# CristmasVillage_Driver_1-1.net
KiCad netlist of a schematic drawn in EAGLE
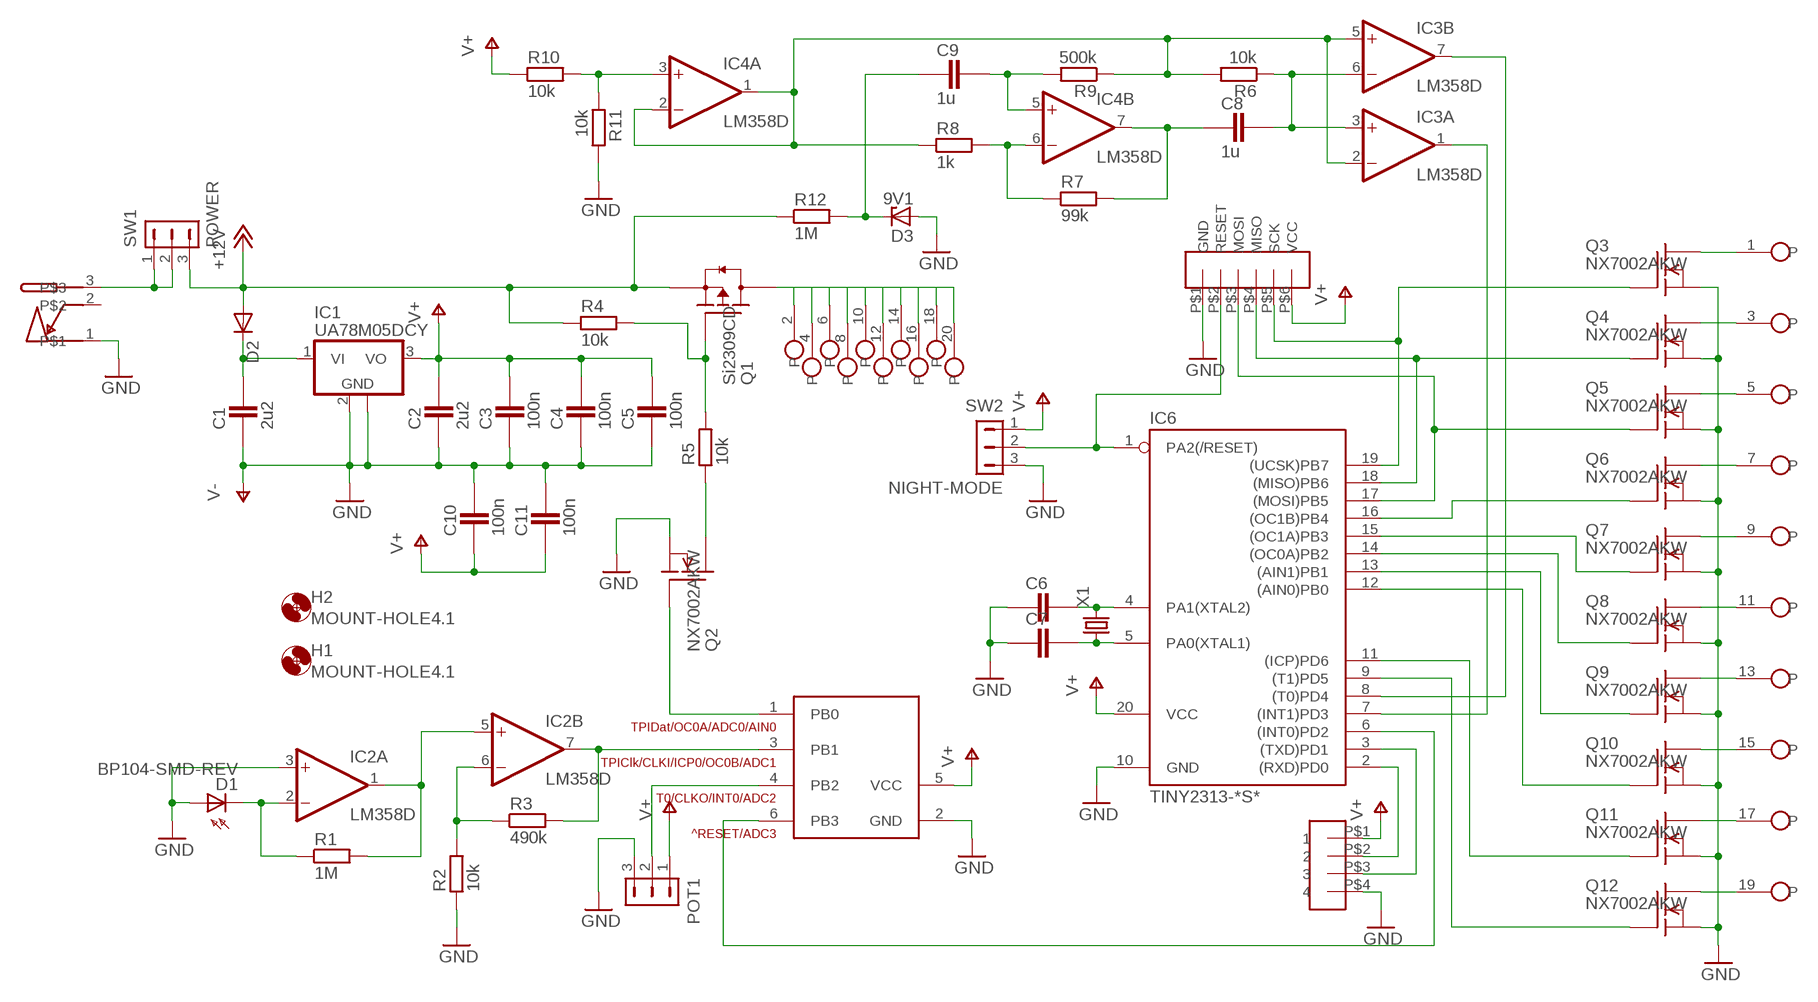
[diagram p0: schematic, sheet 1]

(export (version "E")
  (design (tool "Eeschema 10.0.6"))
  (components
    (comp (ref "C1")
      (value "2u2")
      (footprint "eagle-import:CAPC3215X168N")
      (libsource (lib "eagle-import") (part "CAPACITOR_1206"))
    )
    (comp (ref "C2")
      (value "2u2")
      (footprint "eagle-import:CAPC3215X168N")
      (libsource (lib "eagle-import") (part "CAPACITOR_1206"))
    )
    (comp (ref "C3")
      (value "100n")
      (footprint "eagle-import:CAPC1608X92N")
      (libsource (lib "eagle-import") (part "CAPACITOR_0603"))
    )
    (comp (ref "C4")
      (value "100n")
      (footprint "eagle-import:CAPC1608X92N")
      (libsource (lib "eagle-import") (part "CAPACITOR_0603"))
    )
    (comp (ref "C5")
      (value "100n")
      (footprint "eagle-import:CAPC1608X92N")
      (libsource (lib "eagle-import") (part "CAPACITOR_0603"))
    )
    (comp (ref "C6")
      (value "CAPACITOR_0603")
      (footprint "eagle-import:CAPC1608X92N")
      (libsource (lib "eagle-import") (part "CAPACITOR_0603"))
    )
    (comp (ref "C7")
      (value "CAPACITOR_0603")
      (footprint "eagle-import:CAPC1608X92N")
      (libsource (lib "eagle-import") (part "CAPACITOR_0603"))
    )
    (comp (ref "C8")
      (value "1u")
      (footprint "eagle-import:CAPC3215X168N")
      (libsource (lib "eagle-import") (part "CAPACITOR_1206"))
    )
    (comp (ref "C9")
      (value "1u")
      (footprint "eagle-import:CAPC3215X168N")
      (libsource (lib "eagle-import") (part "CAPACITOR_1206"))
    )
    (comp (ref "C10")
      (value "100n")
      (footprint "eagle-import:CAPC1608X92N")
      (libsource (lib "eagle-import") (part "CAPACITOR_0603"))
    )
    (comp (ref "C11")
      (value "100n")
      (footprint "eagle-import:CAPC1608X92N")
      (libsource (lib "eagle-import") (part "CAPACITOR_0603"))
    )
    (comp (ref "CN1")
      (value "MJ-180SMT")
      (footprint "eagle-import:MJ-180SMT")
      (libsource (lib "eagle-import") (part "MJ-180SMT"))
    )
    (comp (ref "CN2-PROG")
      (value "JST-6PSPI-SIDE-S6B")
      (footprint "eagle-import:6P-H")
      (libsource (lib "eagle-import") (part "JST-6PSPI-SIDE-S6B"))
    )
    (comp (ref "CN3-SERIAL")
      (value "JST-4PSIDE-S4B")
      (footprint "eagle-import:4P-H")
      (libsource (lib "eagle-import") (part "JST-4PSIDE-S4B"))
    )
    (comp (ref "CN5-LEDSTRIPS")
      (value "HDR_2X10_SIDE-MOUNT")
      (footprint "eagle-import:20PIN-10TOP-10BOT")
      (libsource (lib "eagle-import") (part "HDR_2X10_SIDE-MOUNT"))
    )
    (comp (ref "D1")
      (value "BP104-SMD-REV")
      (footprint "eagle-import:BR104SMDREV")
      (libsource (lib "eagle-import") (part "BP104-SMD-REV"))
    )
    (comp (ref "D2")
      (value "DIODE-MINIMELF")
      (footprint "eagle-import:MINIMELF")
      (libsource (lib "eagle-import") (part "DIODE-MINIMELF"))
    )
    (comp (ref "D3")
      (value "9V1")
      (footprint "eagle-import:SOT23")
      (libsource (lib "eagle-import") (part "ZENER-DIODESOT23"))
    )
    (comp (ref "H1")
      (value "MOUNT-HOLE4.1")
      (footprint "eagle-import:4,1")
      (libsource (lib "eagle-import") (part "MOUNT-HOLE4.1"))
    )
    (comp (ref "H2")
      (value "MOUNT-HOLE4.1")
      (footprint "eagle-import:4,1")
      (libsource (lib "eagle-import") (part "MOUNT-HOLE4.1"))
    )
    (comp (ref "IC1")
      (value "UA78M05DCY")
      (footprint "eagle-import:SOT223")
      (libsource (lib "eagle-import") (part "UA78MDCY05"))
    )
    (comp (ref "IC2")
      (value "LM358D")
      (footprint "eagle-import:SO08")
      (libsource (lib "eagle-import") (part "LM358D"))
    )
    (comp (ref "IC3")
      (value "LM358D")
      (footprint "eagle-import:SO08")
      (libsource (lib "eagle-import") (part "LM358D"))
    )
    (comp (ref "IC4")
      (value "LM358D")
      (footprint "eagle-import:SO08")
      (libsource (lib "eagle-import") (part "LM358D"))
    )
    (comp (ref "IC5")
      (value "ATTINY-4/5/9/10")
      (footprint "eagle-import:SOT23-6")
      (libsource (lib "eagle-import") (part "ATTINY-4/5/9/10"))
    )
    (comp (ref "IC6")
      (value "TINY2313-*S*")
      (footprint "eagle-import:SO20L$")
      (libsource (lib "eagle-import") (part "TINY2313-S"))
    )
    (comp (ref "POT1")
      (value "HDR-1X3-MTE-100")
      (footprint "eagle-import:MTE-100-3V")
      (libsource (lib "eagle-import") (part "HDR-1X3-MTE-100"))
    )
    (comp (ref "Q1")
      (value "Si2309CD")
      (footprint "eagle-import:SOT95P280X135-3N")
      (libsource (lib "eagle-import") (part "MOSFET-PCH_SOT-23"))
    )
    (comp (ref "Q2")
      (value "NX7002AKW")
      (footprint "eagle-import:SOT323R")
      (libsource (lib "eagle-import") (part "NX7002AKW"))
    )
    (comp (ref "Q3")
      (value "NX7002AKW")
      (footprint "eagle-import:SOT323R")
      (libsource (lib "eagle-import") (part "NX7002AKW"))
    )
    (comp (ref "Q4")
      (value "NX7002AKW")
      (footprint "eagle-import:SOT323R")
      (libsource (lib "eagle-import") (part "NX7002AKW"))
    )
    (comp (ref "Q5")
      (value "NX7002AKW")
      (footprint "eagle-import:SOT323R")
      (libsource (lib "eagle-import") (part "NX7002AKW"))
    )
    (comp (ref "Q6")
      (value "NX7002AKW")
      (footprint "eagle-import:SOT323R")
      (libsource (lib "eagle-import") (part "NX7002AKW"))
    )
    (comp (ref "Q7")
      (value "NX7002AKW")
      (footprint "eagle-import:SOT323R")
      (libsource (lib "eagle-import") (part "NX7002AKW"))
    )
    (comp (ref "Q8")
      (value "NX7002AKW")
      (footprint "eagle-import:SOT323R")
      (libsource (lib "eagle-import") (part "NX7002AKW"))
    )
    (comp (ref "Q9")
      (value "NX7002AKW")
      (footprint "eagle-import:SOT323R")
      (libsource (lib "eagle-import") (part "NX7002AKW"))
    )
    (comp (ref "Q10")
      (value "NX7002AKW")
      (footprint "eagle-import:SOT323R")
      (libsource (lib "eagle-import") (part "NX7002AKW"))
    )
    (comp (ref "Q11")
      (value "NX7002AKW")
      (footprint "eagle-import:SOT323R")
      (libsource (lib "eagle-import") (part "NX7002AKW"))
    )
    (comp (ref "Q12")
      (value "NX7002AKW")
      (footprint "eagle-import:SOT323R")
      (libsource (lib "eagle-import") (part "NX7002AKW"))
    )
    (comp (ref "R1")
      (value "1M")
      (footprint "eagle-import:RESC1608X55N")
      (libsource (lib "eagle-import") (part "RESISTOR_0603"))
    )
    (comp (ref "R2")
      (value "10k")
      (footprint "eagle-import:RESC1608X55N")
      (libsource (lib "eagle-import") (part "RESISTOR_0603"))
    )
    (comp (ref "R3")
      (value "490k")
      (footprint "eagle-import:RESC1608X55N")
      (libsource (lib "eagle-import") (part "RESISTOR_0603"))
    )
    (comp (ref "R4")
      (value "10k")
      (footprint "eagle-import:RESC1608X55N")
      (libsource (lib "eagle-import") (part "RESISTOR_0603"))
    )
    (comp (ref "R5")
      (value "10k")
      (footprint "eagle-import:RESC1608X55N")
      (libsource (lib "eagle-import") (part "RESISTOR_0603"))
    )
    (comp (ref "R6")
      (value "10k")
      (footprint "eagle-import:RESC1608X55N")
      (libsource (lib "eagle-import") (part "RESISTOR_0603"))
    )
    (comp (ref "R7")
      (value "99k")
      (footprint "eagle-import:RESC1608X55N")
      (libsource (lib "eagle-import") (part "RESISTOR_0603"))
    )
    (comp (ref "R8")
      (value "1k")
      (footprint "eagle-import:RESC1608X55N")
      (libsource (lib "eagle-import") (part "RESISTOR_0603"))
    )
    (comp (ref "R9")
      (value "500k")
      (footprint "eagle-import:RESC1608X55N")
      (libsource (lib "eagle-import") (part "RESISTOR_0603"))
    )
    (comp (ref "R10")
      (value "10k")
      (footprint "eagle-import:RESC1608X55N")
      (libsource (lib "eagle-import") (part "RESISTOR_0603"))
    )
    (comp (ref "R11")
      (value "10k")
      (footprint "eagle-import:RESC1608X55N")
      (libsource (lib "eagle-import") (part "RESISTOR_0603"))
    )
    (comp (ref "R12")
      (value "1M")
      (footprint "eagle-import:RESC1608X55N")
      (libsource (lib "eagle-import") (part "RESISTOR_0603"))
    )
    (comp (ref "SW1")
      (value "POWER")
      (footprint "eagle-import:MTE-100-3V")
      (libsource (lib "eagle-import") (part "HDR-1X3-MTE-100"))
    )
    (comp (ref "SW2")
      (value "NIGHT-MODE")
      (footprint "eagle-import:MTE-100-3V")
      (libsource (lib "eagle-import") (part "HDR-1X3-MTE-100"))
    )
    (comp (ref "X1")
      (value "CRYSTALSM49")
      (footprint "eagle-import:SM49")
      (libsource (lib "eagle-import") (part "CRYSTALSM49"))
    )
  )
  (nets
    (net (code "1") (name "+12V") (class "Default")
      (node (ref "D2") (pin "A") (pinfunction "A_A") (pintype "passive"))
      (node (ref "Q1") (pin "2") (pinfunction "S_2") (pintype "passive"))
      (node (ref "R12") (pin "1") (pinfunction "1_1") (pintype "passive"))
      (node (ref "R4") (pin "1") (pinfunction "1_1") (pintype "passive"))
      (node (ref "SW1") (pin "3") (pinfunction "3_3") (pintype "passive"))
    )
    (net (code "2") (name "GND") (class "Default")
      (node (ref "C1") (pin "1") (pinfunction "1_1") (pintype "passive"))
      (node (ref "C10") (pin "2") (pinfunction "2_2") (pintype "passive"))
      (node (ref "C11") (pin "2") (pinfunction "2_2") (pintype "passive"))
      (node (ref "C2") (pin "1") (pinfunction "1_1") (pintype "passive"))
      (node (ref "C3") (pin "1") (pinfunction "1_1") (pintype "passive"))
      (node (ref "C4") (pin "1") (pinfunction "1_1") (pintype "passive"))
      (node (ref "C5") (pin "1") (pinfunction "1_1") (pintype "passive"))
      (node (ref "C6") (pin "1") (pinfunction "1_1") (pintype "passive"))
      (node (ref "C7") (pin "1") (pinfunction "1_1") (pintype "passive"))
      (node (ref "CN1") (pin "1") (pinfunction "P$1_1") (pintype "bidirectional"))
      (node (ref "CN2-PROG") (pin "P$1") (pinfunction "GND_P$1") (pintype "bidirectional"))
      (node (ref "CN3-SERIAL") (pin "P$4") (pinfunction "4_P$4") (pintype "bidirectional"))
      (node (ref "D1") (pin "1") (pinfunction "A_1") (pintype "passive"))
      (node (ref "D3") (pin "1") (pinfunction "A_1") (pintype "passive"))
      (node (ref "IC1") (pin "2") (pinfunction "GND_2") (pintype "passive"))
      (node (ref "IC1") (pin "4") (pinfunction "GND_4") (pintype "passive"))
      (node (ref "IC2") (pin "3") (pinfunction "+IN_3") (pintype "input"))
      (node (ref "IC5") (pin "2") (pinfunction "GND_2") (pintype "bidirectional"))
      (node (ref "IC6") (pin "10") (pinfunction "GND_10") (pintype "power_in"))
      (node (ref "POT1") (pin "3") (pinfunction "3_3") (pintype "passive"))
      (node (ref "Q10") (pin "2") (pinfunction "S_2") (pintype "passive"))
      (node (ref "Q11") (pin "2") (pinfunction "S_2") (pintype "passive"))
      (node (ref "Q12") (pin "2") (pinfunction "S_2") (pintype "passive"))
      (node (ref "Q2") (pin "2") (pinfunction "S_2") (pintype "passive"))
      (node (ref "Q3") (pin "2") (pinfunction "S_2") (pintype "passive"))
      (node (ref "Q4") (pin "2") (pinfunction "S_2") (pintype "passive"))
      (node (ref "Q5") (pin "2") (pinfunction "S_2") (pintype "passive"))
      (node (ref "Q6") (pin "2") (pinfunction "S_2") (pintype "passive"))
      (node (ref "Q7") (pin "2") (pinfunction "S_2") (pintype "passive"))
      (node (ref "Q8") (pin "2") (pinfunction "S_2") (pintype "passive"))
      (node (ref "Q9") (pin "2") (pinfunction "S_2") (pintype "passive"))
      (node (ref "R11") (pin "2") (pinfunction "2_2") (pintype "passive"))
      (node (ref "R2") (pin "1") (pinfunction "1_1") (pintype "passive"))
      (node (ref "SW2") (pin "3") (pinfunction "3_3") (pintype "passive"))
    )
    (net (code "3") (name "Net-(CN1-P$3)") (class "Default")
      (node (ref "CN1") (pin "3") (pinfunction "P$3_3") (pintype "bidirectional"))
      (node (ref "SW1") (pin "1") (pinfunction "1_1") (pintype "passive"))
      (node (ref "SW1") (pin "2") (pinfunction "2_2") (pintype "passive"))
    )
    (net (code "4") (name "Net-(CN2-PROG-MISO)") (class "Default")
      (node (ref "CN2-PROG") (pin "P$4") (pinfunction "MISO_P$4") (pintype "bidirectional"))
      (node (ref "IC6") (pin "18") (pinfunction "(MISO)PB6_18") (pintype "bidirectional"))
      (node (ref "Q4") (pin "1") (pinfunction "G_1") (pintype "passive"))
    )
    (net (code "5") (name "Net-(CN2-PROG-MOSI)") (class "Default")
      (node (ref "CN2-PROG") (pin "P$3") (pinfunction "MOSI_P$3") (pintype "bidirectional"))
      (node (ref "IC6") (pin "17") (pinfunction "(MOSI)PB5_17") (pintype "bidirectional"))
      (node (ref "Q5") (pin "1") (pinfunction "G_1") (pintype "passive"))
    )
    (net (code "6") (name "Net-(CN2-PROG-RESET)") (class "Default")
      (node (ref "CN2-PROG") (pin "P$2") (pinfunction "RESET_P$2") (pintype "bidirectional"))
      (node (ref "IC6") (pin "1") (pinfunction "PA2(/RESET)_1") (pintype "input"))
      (node (ref "SW2") (pin "2") (pinfunction "2_2") (pintype "passive"))
    )
    (net (code "7") (name "Net-(CN2-PROG-SCK)") (class "Default")
      (node (ref "CN2-PROG") (pin "P$5") (pinfunction "SCK_P$5") (pintype "bidirectional"))
      (node (ref "IC6") (pin "19") (pinfunction "(UCSK)PB7_19") (pintype "bidirectional"))
      (node (ref "Q3") (pin "1") (pinfunction "G_1") (pintype "passive"))
    )
    (net (code "8") (name "Net-(CN3-SERIAL-2)") (class "Default")
      (node (ref "CN3-SERIAL") (pin "P$2") (pinfunction "2_P$2") (pintype "bidirectional"))
      (node (ref "IC6") (pin "2") (pinfunction "(RXD)PD0_2") (pintype "bidirectional"))
    )
    (net (code "9") (name "Net-(CN3-SERIAL-3)") (class "Default")
      (node (ref "CN3-SERIAL") (pin "P$3") (pinfunction "3_P$3") (pintype "bidirectional"))
      (node (ref "IC6") (pin "3") (pinfunction "(TXD)PD1_3") (pintype "bidirectional"))
    )
    (net (code "10") (name "Net-(CN5-LEDSTRIPSA-P)") (class "Default")
      (node (ref "CN5-LEDSTRIPS") (pin "1") (pinfunction "P_1") (pintype "bidirectional"))
      (node (ref "Q3") (pin "3") (pinfunction "D_3") (pintype "passive"))
    )
    (net (code "11") (name "Net-(CN5-LEDSTRIPSB-P)") (class "Default")
      (node (ref "CN5-LEDSTRIPS") (pin "10") (pinfunction "P_10") (pintype "bidirectional"))
      (node (ref "CN5-LEDSTRIPS") (pin "12") (pinfunction "P_12") (pintype "bidirectional"))
      (node (ref "CN5-LEDSTRIPS") (pin "14") (pinfunction "P_14") (pintype "bidirectional"))
      (node (ref "CN5-LEDSTRIPS") (pin "16") (pinfunction "P_16") (pintype "bidirectional"))
      (node (ref "CN5-LEDSTRIPS") (pin "18") (pinfunction "P_18") (pintype "bidirectional"))
      (node (ref "CN5-LEDSTRIPS") (pin "2") (pinfunction "P_2") (pintype "bidirectional"))
      (node (ref "CN5-LEDSTRIPS") (pin "20") (pinfunction "P_20") (pintype "bidirectional"))
      (node (ref "CN5-LEDSTRIPS") (pin "4") (pinfunction "P_4") (pintype "bidirectional"))
      (node (ref "CN5-LEDSTRIPS") (pin "6") (pinfunction "P_6") (pintype "bidirectional"))
      (node (ref "CN5-LEDSTRIPS") (pin "8") (pinfunction "P_8") (pintype "bidirectional"))
      (node (ref "Q1") (pin "3") (pinfunction "D_3") (pintype "passive"))
    )
    (net (code "12") (name "Net-(CN5-LEDSTRIPSC-P)") (class "Default")
      (node (ref "CN5-LEDSTRIPS") (pin "11") (pinfunction "P_11") (pintype "bidirectional"))
      (node (ref "Q8") (pin "3") (pinfunction "D_3") (pintype "passive"))
    )
    (net (code "13") (name "Net-(CN5-LEDSTRIPSE-P)") (class "Default")
      (node (ref "CN5-LEDSTRIPS") (pin "13") (pinfunction "P_13") (pintype "bidirectional"))
      (node (ref "Q9") (pin "3") (pinfunction "D_3") (pintype "passive"))
    )
    (net (code "14") (name "Net-(CN5-LEDSTRIPSG-P)") (class "Default")
      (node (ref "CN5-LEDSTRIPS") (pin "15") (pinfunction "P_15") (pintype "bidirectional"))
      (node (ref "Q10") (pin "3") (pinfunction "D_3") (pintype "passive"))
    )
    (net (code "15") (name "Net-(CN5-LEDSTRIPSI-P)") (class "Default")
      (node (ref "CN5-LEDSTRIPS") (pin "17") (pinfunction "P_17") (pintype "bidirectional"))
      (node (ref "Q11") (pin "3") (pinfunction "D_3") (pintype "passive"))
    )
    (net (code "16") (name "Net-(CN5-LEDSTRIPSK-P)") (class "Default")
      (node (ref "CN5-LEDSTRIPS") (pin "19") (pinfunction "P_19") (pintype "bidirectional"))
      (node (ref "Q12") (pin "3") (pinfunction "D_3") (pintype "passive"))
    )
    (net (code "17") (name "Net-(CN5-LEDSTRIPSN-P)") (class "Default")
      (node (ref "CN5-LEDSTRIPS") (pin "3") (pinfunction "P_3") (pintype "bidirectional"))
      (node (ref "Q4") (pin "3") (pinfunction "D_3") (pintype "passive"))
    )
    (net (code "18") (name "Net-(CN5-LEDSTRIPSP-P)") (class "Default")
      (node (ref "CN5-LEDSTRIPS") (pin "5") (pinfunction "P_5") (pintype "bidirectional"))
      (node (ref "Q5") (pin "3") (pinfunction "D_3") (pintype "passive"))
    )
    (net (code "19") (name "Net-(CN5-LEDSTRIPSR-P)") (class "Default")
      (node (ref "CN5-LEDSTRIPS") (pin "7") (pinfunction "P_7") (pintype "bidirectional"))
      (node (ref "Q6") (pin "3") (pinfunction "D_3") (pintype "passive"))
    )
    (net (code "20") (name "Net-(CN5-LEDSTRIPST-P)") (class "Default")
      (node (ref "CN5-LEDSTRIPS") (pin "9") (pinfunction "P_9") (pintype "bidirectional"))
      (node (ref "Q7") (pin "3") (pinfunction "D_3") (pintype "passive"))
    )
    (net (code "21") (name "Net-(D1-C)") (class "Default")
      (node (ref "D1") (pin "2") (pinfunction "C_2") (pintype "passive"))
      (node (ref "IC2") (pin "2") (pinfunction "-IN_2") (pintype "input"))
      (node (ref "R1") (pin "1") (pinfunction "1_1") (pintype "passive"))
    )
    (net (code "22") (name "Net-(D3-C)") (class "Default")
      (node (ref "C9") (pin "1") (pinfunction "1_1") (pintype "passive"))
      (node (ref "D3") (pin "3") (pinfunction "C_3") (pintype "passive"))
      (node (ref "R12") (pin "2") (pinfunction "2_2") (pintype "passive"))
    )
    (net (code "23") (name "Net-(IC1-VI)") (class "Default")
      (node (ref "C1") (pin "2") (pinfunction "2_2") (pintype "passive"))
      (node (ref "D2") (pin "C") (pinfunction "C_C") (pintype "passive"))
      (node (ref "IC1") (pin "1") (pinfunction "VI_1") (pintype "input"))
    )
    (net (code "24") (name "Net-(IC2A-OUT)") (class "Default")
      (node (ref "IC2") (pin "1") (pinfunction "OUT_1") (pintype "output"))
      (node (ref "IC2") (pin "5") (pinfunction "+IN_5") (pintype "input"))
      (node (ref "R1") (pin "2") (pinfunction "2_2") (pintype "passive"))
    )
    (net (code "25") (name "Net-(IC2B--IN)") (class "Default")
      (node (ref "IC2") (pin "6") (pinfunction "-IN_6") (pintype "input"))
      (node (ref "R2") (pin "2") (pinfunction "2_2") (pintype "passive"))
      (node (ref "R3") (pin "1") (pinfunction "1_1") (pintype "passive"))
    )
    (net (code "26") (name "Net-(IC2B-OUT)") (class "Default")
      (node (ref "IC2") (pin "7") (pinfunction "OUT_7") (pintype "output"))
      (node (ref "IC5") (pin "3") (pinfunction "PB1_3") (pintype "bidirectional"))
      (node (ref "R3") (pin "2") (pinfunction "2_2") (pintype "passive"))
    )
    (net (code "27") (name "Net-(IC3A-+IN)") (class "Default")
      (node (ref "C8") (pin "2") (pinfunction "2_2") (pintype "passive"))
      (node (ref "IC3") (pin "3") (pinfunction "+IN_3") (pintype "input"))
      (node (ref "IC3") (pin "6") (pinfunction "-IN_6") (pintype "input"))
      (node (ref "R6") (pin "1") (pinfunction "1_1") (pintype "passive"))
    )
    (net (code "28") (name "Net-(IC3A--IN)") (class "Default")
      (node (ref "IC3") (pin "2") (pinfunction "-IN_2") (pintype "input"))
      (node (ref "IC3") (pin "5") (pinfunction "+IN_5") (pintype "input"))
      (node (ref "IC4") (pin "1") (pinfunction "OUT_1") (pintype "output"))
      (node (ref "IC4") (pin "2") (pinfunction "-IN_2") (pintype "input"))
      (node (ref "R6") (pin "2") (pinfunction "2_2") (pintype "passive"))
      (node (ref "R8") (pin "1") (pinfunction "1_1") (pintype "passive"))
      (node (ref "R9") (pin "1") (pinfunction "1_1") (pintype "passive"))
    )
    (net (code "29") (name "Net-(IC3A-OUT)") (class "Default")
      (node (ref "IC3") (pin "1") (pinfunction "OUT_1") (pintype "output"))
      (node (ref "IC6") (pin "7") (pinfunction "(INT1)PD3_7") (pintype "bidirectional"))
    )
    (net (code "30") (name "Net-(IC3B-OUT)") (class "Default")
      (node (ref "IC3") (pin "7") (pinfunction "OUT_7") (pintype "output"))
      (node (ref "IC6") (pin "8") (pinfunction "(T0)PD4_8") (pintype "bidirectional"))
    )
    (net (code "31") (name "Net-(IC4A-+IN)") (class "Default")
      (node (ref "IC4") (pin "3") (pinfunction "+IN_3") (pintype "input"))
      (node (ref "R10") (pin "2") (pinfunction "2_2") (pintype "passive"))
      (node (ref "R11") (pin "1") (pinfunction "1_1") (pintype "passive"))
    )
    (net (code "32") (name "Net-(IC4B-+IN)") (class "Default")
      (node (ref "C9") (pin "2") (pinfunction "2_2") (pintype "passive"))
      (node (ref "IC4") (pin "5") (pinfunction "+IN_5") (pintype "input"))
      (node (ref "R9") (pin "2") (pinfunction "2_2") (pintype "passive"))
    )
    (net (code "33") (name "Net-(IC4B--IN)") (class "Default")
      (node (ref "IC4") (pin "6") (pinfunction "-IN_6") (pintype "input"))
      (node (ref "R7") (pin "1") (pinfunction "1_1") (pintype "passive"))
      (node (ref "R8") (pin "2") (pinfunction "2_2") (pintype "passive"))
    )
    (net (code "34") (name "Net-(IC4B-OUT)") (class "Default")
      (node (ref "C8") (pin "1") (pinfunction "1_1") (pintype "passive"))
      (node (ref "IC4") (pin "7") (pinfunction "OUT_7") (pintype "output"))
      (node (ref "R7") (pin "2") (pinfunction "2_2") (pintype "passive"))
    )
    (net (code "35") (name "Net-(IC5-PB0)") (class "Default")
      (node (ref "IC5") (pin "1") (pinfunction "PB0_1") (pintype "bidirectional"))
      (node (ref "Q2") (pin "1") (pinfunction "G_1") (pintype "passive"))
    )
    (net (code "36") (name "Net-(IC5-PB2)") (class "Default")
      (node (ref "IC5") (pin "4") (pinfunction "PB2_4") (pintype "bidirectional"))
      (node (ref "POT1") (pin "2") (pinfunction "2_2") (pintype "passive"))
    )
    (net (code "37") (name "Net-(IC5-PB3)") (class "Default")
      (node (ref "IC5") (pin "6") (pinfunction "PB3_6") (pintype "bidirectional"))
      (node (ref "IC6") (pin "6") (pinfunction "(INT0)PD2_6") (pintype "bidirectional"))
    )
    (net (code "38") (name "Net-(IC6-(AIN0)PB0)") (class "Default")
      (node (ref "IC6") (pin "12") (pinfunction "(AIN0)PB0_12") (pintype "bidirectional"))
      (node (ref "Q10") (pin "1") (pinfunction "G_1") (pintype "passive"))
    )
    (net (code "39") (name "Net-(IC6-(AIN1)PB1)") (class "Default")
      (node (ref "IC6") (pin "13") (pinfunction "(AIN1)PB1_13") (pintype "bidirectional"))
      (node (ref "Q9") (pin "1") (pinfunction "G_1") (pintype "passive"))
    )
    (net (code "40") (name "Net-(IC6-(ICP)PD6)") (class "Default")
      (node (ref "IC6") (pin "11") (pinfunction "(ICP)PD6_11") (pintype "bidirectional"))
      (node (ref "Q11") (pin "1") (pinfunction "G_1") (pintype "passive"))
    )
    (net (code "41") (name "Net-(IC6-(OC0A)PB2)") (class "Default")
      (node (ref "IC6") (pin "14") (pinfunction "(OC0A)PB2_14") (pintype "bidirectional"))
      (node (ref "Q8") (pin "1") (pinfunction "G_1") (pintype "passive"))
    )
    (net (code "42") (name "Net-(IC6-(OC1A)PB3)") (class "Default")
      (node (ref "IC6") (pin "15") (pinfunction "(OC1A)PB3_15") (pintype "bidirectional"))
      (node (ref "Q7") (pin "1") (pinfunction "G_1") (pintype "passive"))
    )
    (net (code "43") (name "Net-(IC6-(OC1B)PB4)") (class "Default")
      (node (ref "IC6") (pin "16") (pinfunction "(OC1B)PB4_16") (pintype "bidirectional"))
      (node (ref "Q6") (pin "1") (pinfunction "G_1") (pintype "passive"))
    )
    (net (code "44") (name "Net-(IC6-(T1)PD5)") (class "Default")
      (node (ref "IC6") (pin "9") (pinfunction "(T1)PD5_9") (pintype "bidirectional"))
      (node (ref "Q12") (pin "1") (pinfunction "G_1") (pintype "passive"))
    )
    (net (code "45") (name "Net-(IC6-PA0(XTAL1))") (class "Default")
      (node (ref "C7") (pin "2") (pinfunction "2_2") (pintype "passive"))
      (node (ref "IC6") (pin "5") (pinfunction "PA0(XTAL1)_5") (pintype "bidirectional"))
      (node (ref "X1") (pin "1") (pinfunction "1_1") (pintype "passive"))
    )
    (net (code "46") (name "Net-(IC6-PA1(XTAL2))") (class "Default")
      (node (ref "C6") (pin "2") (pinfunction "2_2") (pintype "passive"))
      (node (ref "IC6") (pin "4") (pinfunction "PA1(XTAL2)_4") (pintype "bidirectional"))
      (node (ref "X1") (pin "2") (pinfunction "2_2") (pintype "passive"))
    )
    (net (code "47") (name "Net-(Q1-G)") (class "Default")
      (node (ref "Q1") (pin "1") (pinfunction "G_1") (pintype "passive"))
      (node (ref "R4") (pin "2") (pinfunction "2_2") (pintype "passive"))
      (node (ref "R5") (pin "2") (pinfunction "2_2") (pintype "passive"))
    )
    (net (code "48") (name "Net-(Q2-D)") (class "Default")
      (node (ref "Q2") (pin "3") (pinfunction "D_3") (pintype "passive"))
      (node (ref "R5") (pin "1") (pinfunction "1_1") (pintype "passive"))
    )
    (net (code "49") (name "V+") (class "Default")
      (node (ref "C10") (pin "1") (pinfunction "1_1") (pintype "passive"))
      (node (ref "C11") (pin "1") (pinfunction "1_1") (pintype "passive"))
      (node (ref "C2") (pin "2") (pinfunction "2_2") (pintype "passive"))
      (node (ref "C3") (pin "2") (pinfunction "2_2") (pintype "passive"))
      (node (ref "C4") (pin "2") (pinfunction "2_2") (pintype "passive"))
      (node (ref "C5") (pin "2") (pinfunction "2_2") (pintype "passive"))
      (node (ref "CN2-PROG") (pin "P$6") (pinfunction "VCC_P$6") (pintype "bidirectional"))
      (node (ref "CN3-SERIAL") (pin "P$1") (pinfunction "1_P$1") (pintype "bidirectional"))
      (node (ref "IC1") (pin "3") (pinfunction "VO_3") (pintype "passive"))
      (node (ref "IC5") (pin "5") (pinfunction "VCC_5") (pintype "bidirectional"))
      (node (ref "IC6") (pin "20") (pinfunction "VCC_20") (pintype "power_in"))
      (node (ref "POT1") (pin "1") (pinfunction "1_1") (pintype "passive"))
      (node (ref "R10") (pin "1") (pinfunction "1_1") (pintype "passive"))
      (node (ref "SW2") (pin "1") (pinfunction "1_1") (pintype "passive"))
    )
    (net (code "50") (name "unconnected-(CN1-P$2-Pad2)") (class "Default")
      (node (ref "CN1") (pin "2") (pinfunction "P$2_2") (pintype "bidirectional"))
    )
  )
)
